# twelite.net
KiCad netlist of a schematic drawn in EAGLE
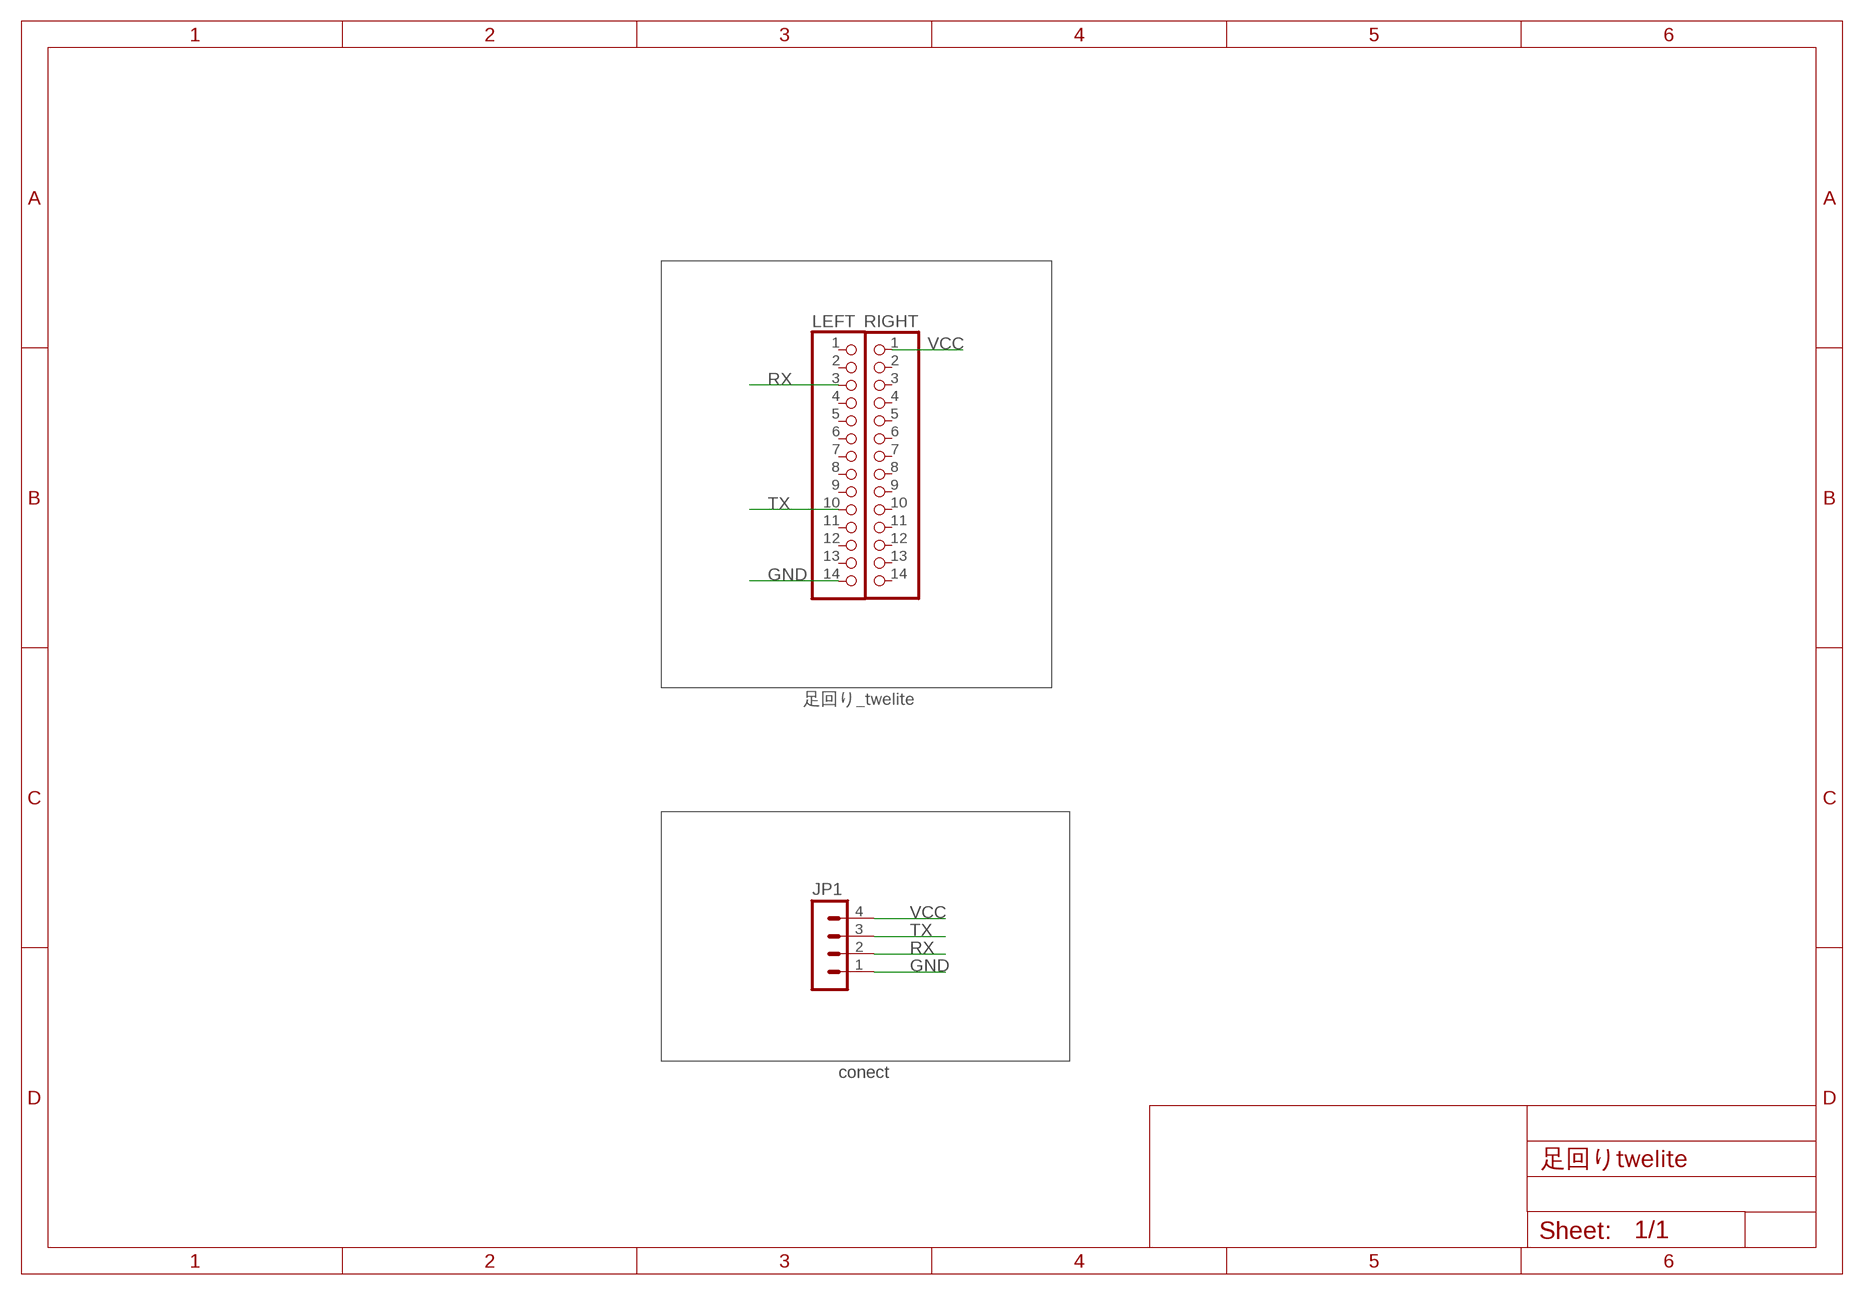
[diagram p0: schematic, sheet 1]

(export (version "E")
  (design (tool "Eeschema 10.0.6"))
  (components
    (comp (ref "JP1")
      (value "04-JST")
      (footprint "eagle-import:B4B-XH")
      (libsource (lib "eagle-import") (part "04-JST"))
    )
    (comp (ref "LEFT")
      (value "PINHD-1X14")
      (footprint "eagle-import:1X14")
      (libsource (lib "eagle-import") (part "PINHD-1X14"))
    )
    (comp (ref "RIGHT")
      (value "PINHD-1X14")
      (footprint "eagle-import:1X14")
      (libsource (lib "eagle-import") (part "PINHD-1X14"))
    )
  )
  (nets
    (net (code "1") (name "/GND") (class "Default")
      (node (ref "JP1") (pin "1") (pinfunction "1_1") (pintype "passive"))
      (node (ref "LEFT") (pin "14") (pinfunction "14_14") (pintype "passive"))
    )
    (net (code "2") (name "/RX") (class "Default")
      (node (ref "JP1") (pin "2") (pinfunction "2_2") (pintype "passive"))
      (node (ref "LEFT") (pin "3") (pinfunction "3_3") (pintype "passive"))
    )
    (net (code "3") (name "/TX") (class "Default")
      (node (ref "JP1") (pin "3") (pinfunction "3_3") (pintype "passive"))
      (node (ref "LEFT") (pin "10") (pinfunction "10_10") (pintype "passive"))
    )
    (net (code "4") (name "/VCC") (class "Default")
      (node (ref "JP1") (pin "4") (pinfunction "4_4") (pintype "passive"))
      (node (ref "RIGHT") (pin "1") (pinfunction "1_1") (pintype "passive"))
    )
    (net (code "5") (name "unconnected-(LEFT-Pad1)") (class "Default")
      (node (ref "LEFT") (pin "1") (pinfunction "1_1") (pintype "passive"))
    )
    (net (code "6") (name "unconnected-(LEFT-Pad2)") (class "Default")
      (node (ref "LEFT") (pin "2") (pinfunction "2_2") (pintype "passive"))
    )
    (net (code "7") (name "unconnected-(LEFT-Pad4)") (class "Default")
      (node (ref "LEFT") (pin "4") (pinfunction "4_4") (pintype "passive"))
    )
    (net (code "8") (name "unconnected-(LEFT-Pad5)") (class "Default")
      (node (ref "LEFT") (pin "5") (pinfunction "5_5") (pintype "passive"))
    )
    (net (code "9") (name "unconnected-(LEFT-Pad6)") (class "Default")
      (node (ref "LEFT") (pin "6") (pinfunction "6_6") (pintype "passive"))
    )
    (net (code "10") (name "unconnected-(LEFT-Pad7)") (class "Default")
      (node (ref "LEFT") (pin "7") (pinfunction "7_7") (pintype "passive"))
    )
    (net (code "11") (name "unconnected-(LEFT-Pad8)") (class "Default")
      (node (ref "LEFT") (pin "8") (pinfunction "8_8") (pintype "passive"))
    )
    (net (code "12") (name "unconnected-(LEFT-Pad9)") (class "Default")
      (node (ref "LEFT") (pin "9") (pinfunction "9_9") (pintype "passive"))
    )
    (net (code "13") (name "unconnected-(LEFT-Pad11)") (class "Default")
      (node (ref "LEFT") (pin "11") (pinfunction "11_11") (pintype "passive"))
    )
    (net (code "14") (name "unconnected-(LEFT-Pad12)") (class "Default")
      (node (ref "LEFT") (pin "12") (pinfunction "12_12") (pintype "passive"))
    )
    (net (code "15") (name "unconnected-(LEFT-Pad13)") (class "Default")
      (node (ref "LEFT") (pin "13") (pinfunction "13_13") (pintype "passive"))
    )
    (net (code "16") (name "unconnected-(RIGHT-Pad2)") (class "Default")
      (node (ref "RIGHT") (pin "2") (pinfunction "2_2") (pintype "passive"))
    )
    (net (code "17") (name "unconnected-(RIGHT-Pad3)") (class "Default")
      (node (ref "RIGHT") (pin "3") (pinfunction "3_3") (pintype "passive"))
    )
    (net (code "18") (name "unconnected-(RIGHT-Pad4)") (class "Default")
      (node (ref "RIGHT") (pin "4") (pinfunction "4_4") (pintype "passive"))
    )
    (net (code "19") (name "unconnected-(RIGHT-Pad5)") (class "Default")
      (node (ref "RIGHT") (pin "5") (pinfunction "5_5") (pintype "passive"))
    )
    (net (code "20") (name "unconnected-(RIGHT-Pad6)") (class "Default")
      (node (ref "RIGHT") (pin "6") (pinfunction "6_6") (pintype "passive"))
    )
    (net (code "21") (name "unconnected-(RIGHT-Pad7)") (class "Default")
      (node (ref "RIGHT") (pin "7") (pinfunction "7_7") (pintype "passive"))
    )
    (net (code "22") (name "unconnected-(RIGHT-Pad8)") (class "Default")
      (node (ref "RIGHT") (pin "8") (pinfunction "8_8") (pintype "passive"))
    )
    (net (code "23") (name "unconnected-(RIGHT-Pad9)") (class "Default")
      (node (ref "RIGHT") (pin "9") (pinfunction "9_9") (pintype "passive"))
    )
    (net (code "24") (name "unconnected-(RIGHT-Pad10)") (class "Default")
      (node (ref "RIGHT") (pin "10") (pinfunction "10_10") (pintype "passive"))
    )
    (net (code "25") (name "unconnected-(RIGHT-Pad11)") (class "Default")
      (node (ref "RIGHT") (pin "11") (pinfunction "11_11") (pintype "passive"))
    )
    (net (code "26") (name "unconnected-(RIGHT-Pad12)") (class "Default")
      (node (ref "RIGHT") (pin "12") (pinfunction "12_12") (pintype "passive"))
    )
    (net (code "27") (name "unconnected-(RIGHT-Pad13)") (class "Default")
      (node (ref "RIGHT") (pin "13") (pinfunction "13_13") (pintype "passive"))
    )
    (net (code "28") (name "unconnected-(RIGHT-Pad14)") (class "Default")
      (node (ref "RIGHT") (pin "14") (pinfunction "14_14") (pintype "passive"))
    )
  )
)
